# can_hub2.net
KiCad netlist of a schematic drawn in EAGLE
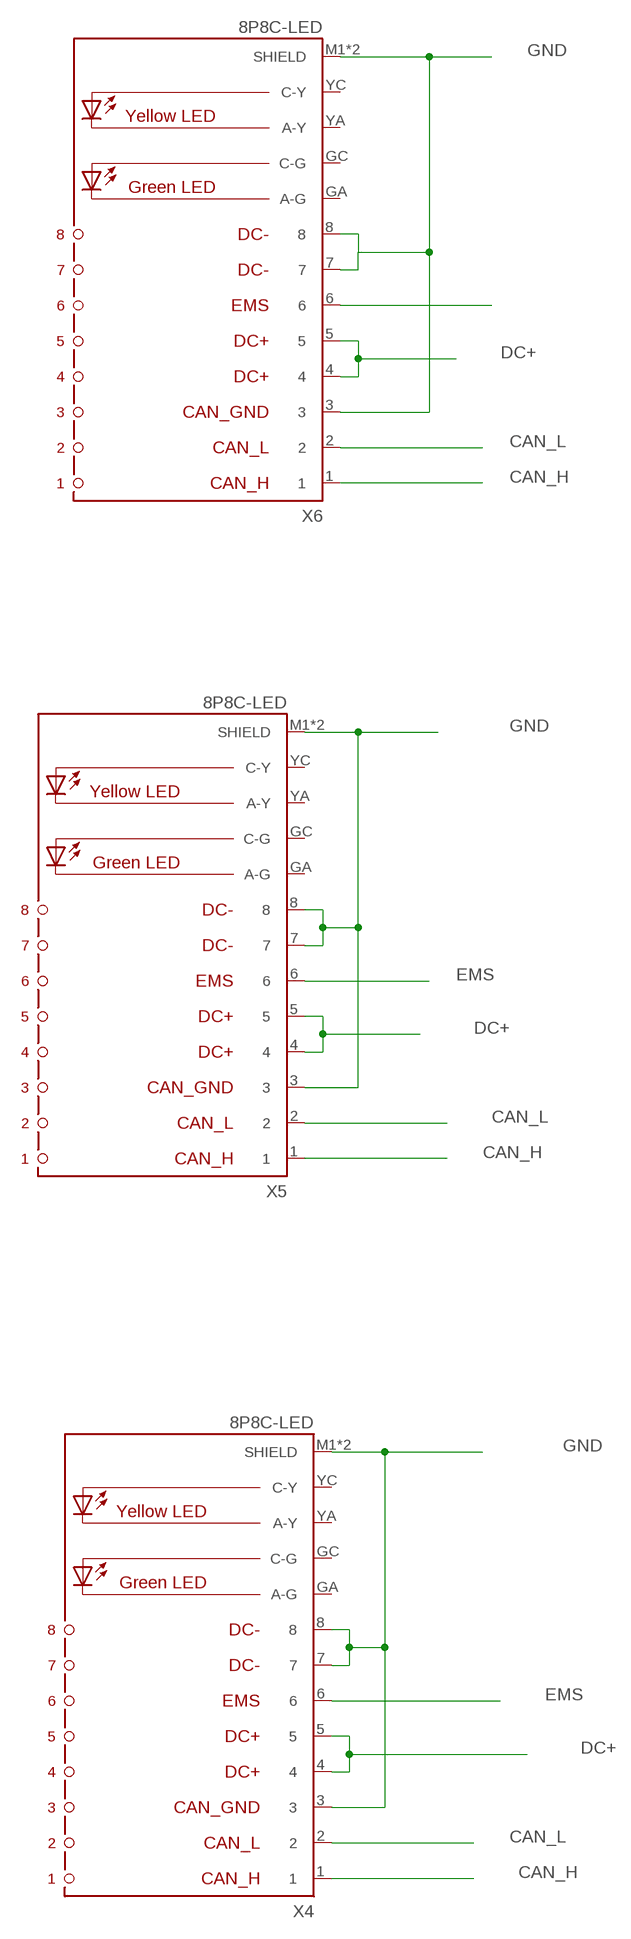
[diagram p0: schematic, sheet 1, part 1 of 3]
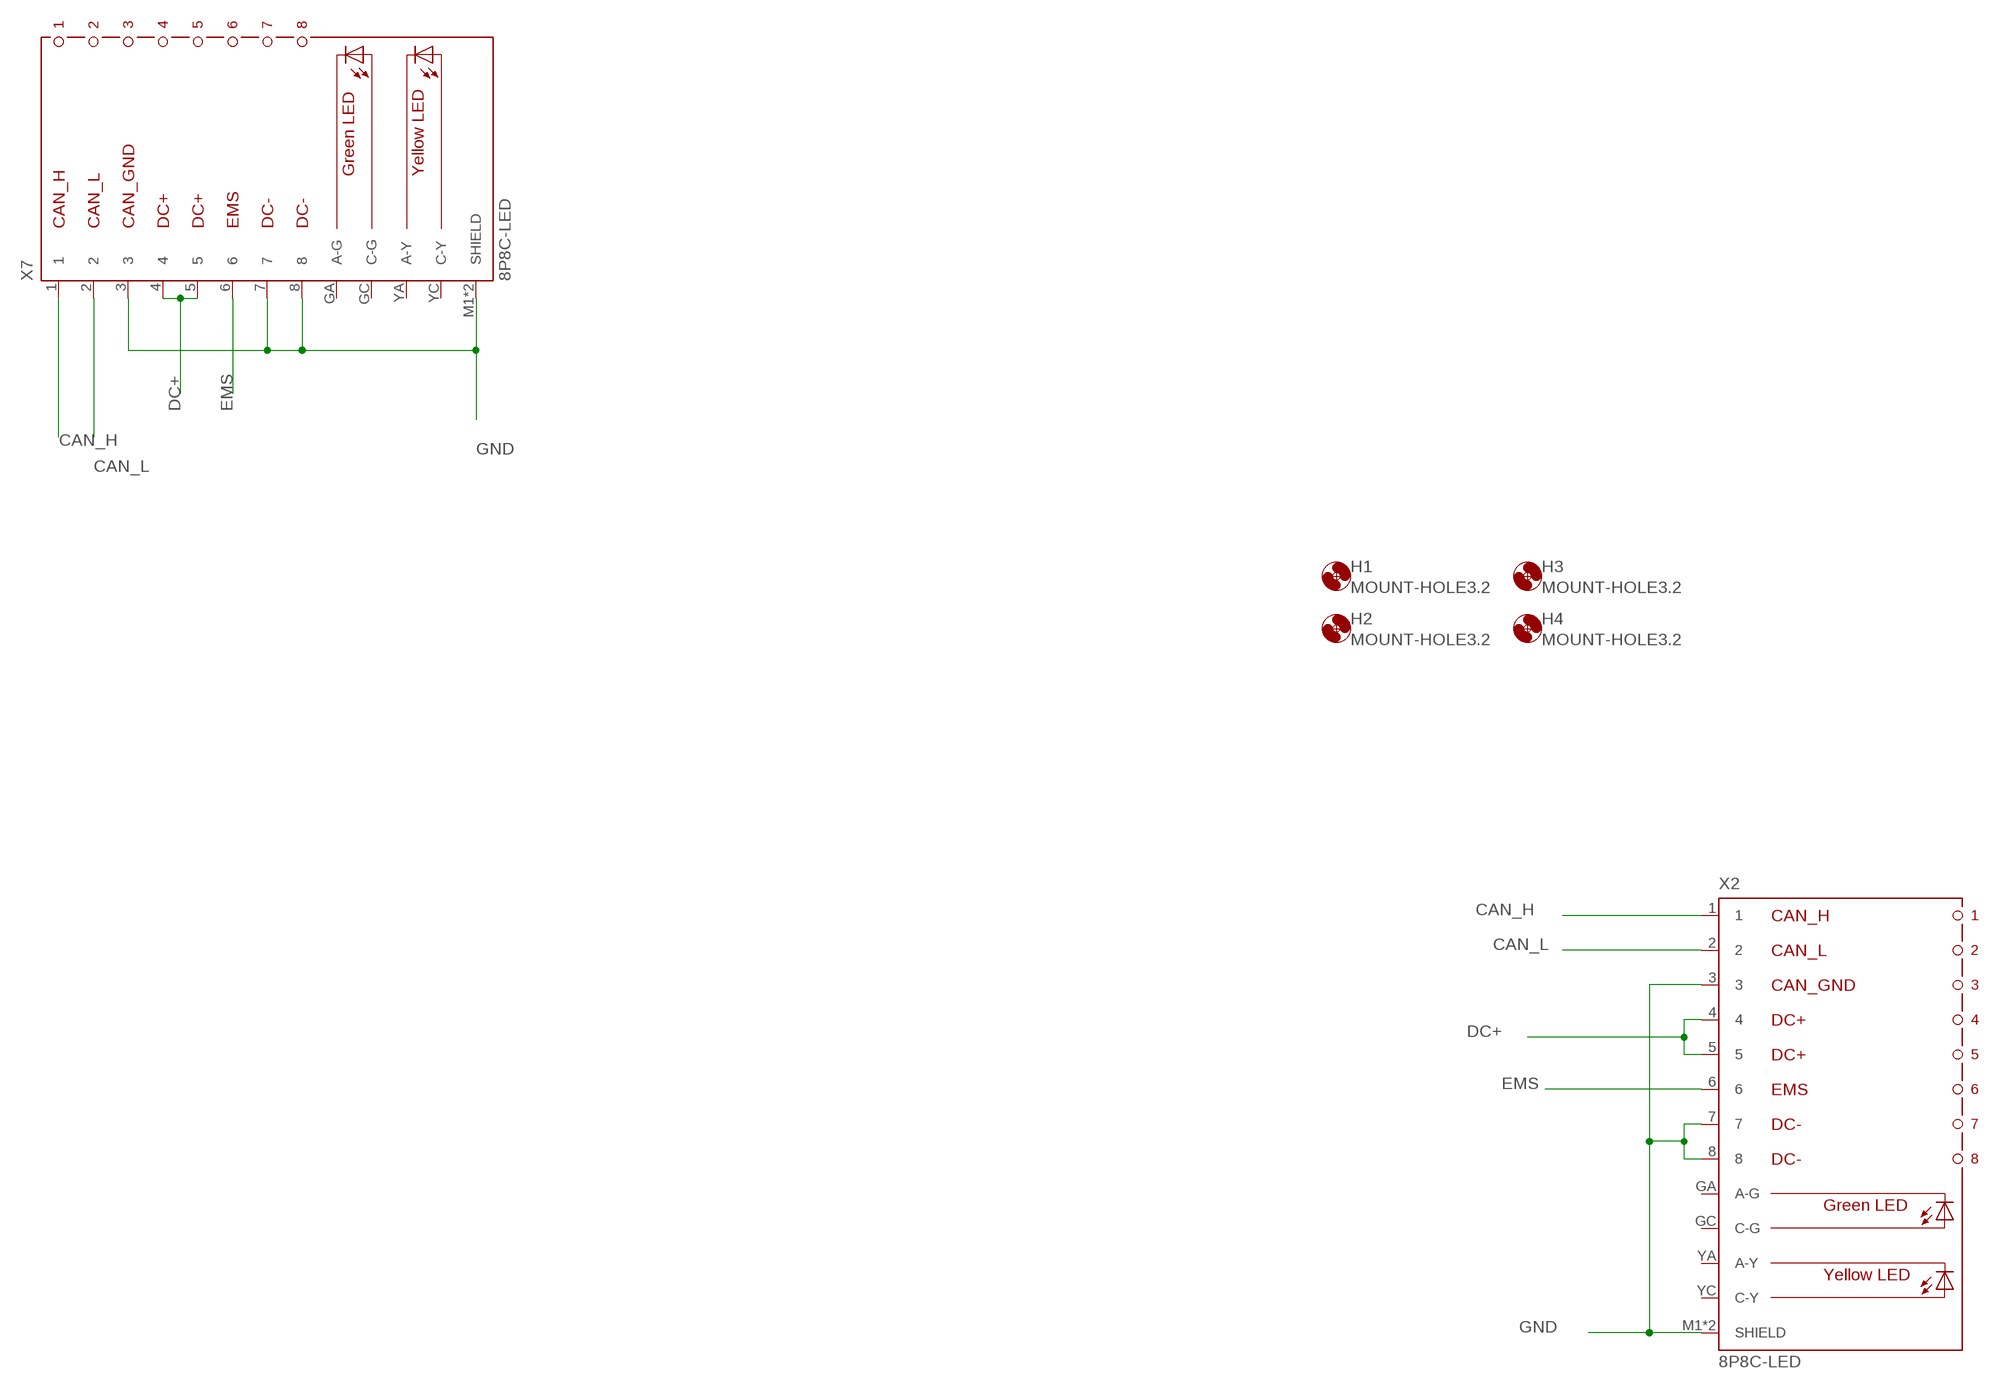
[diagram p1: schematic, sheet 1, part 2 of 3]
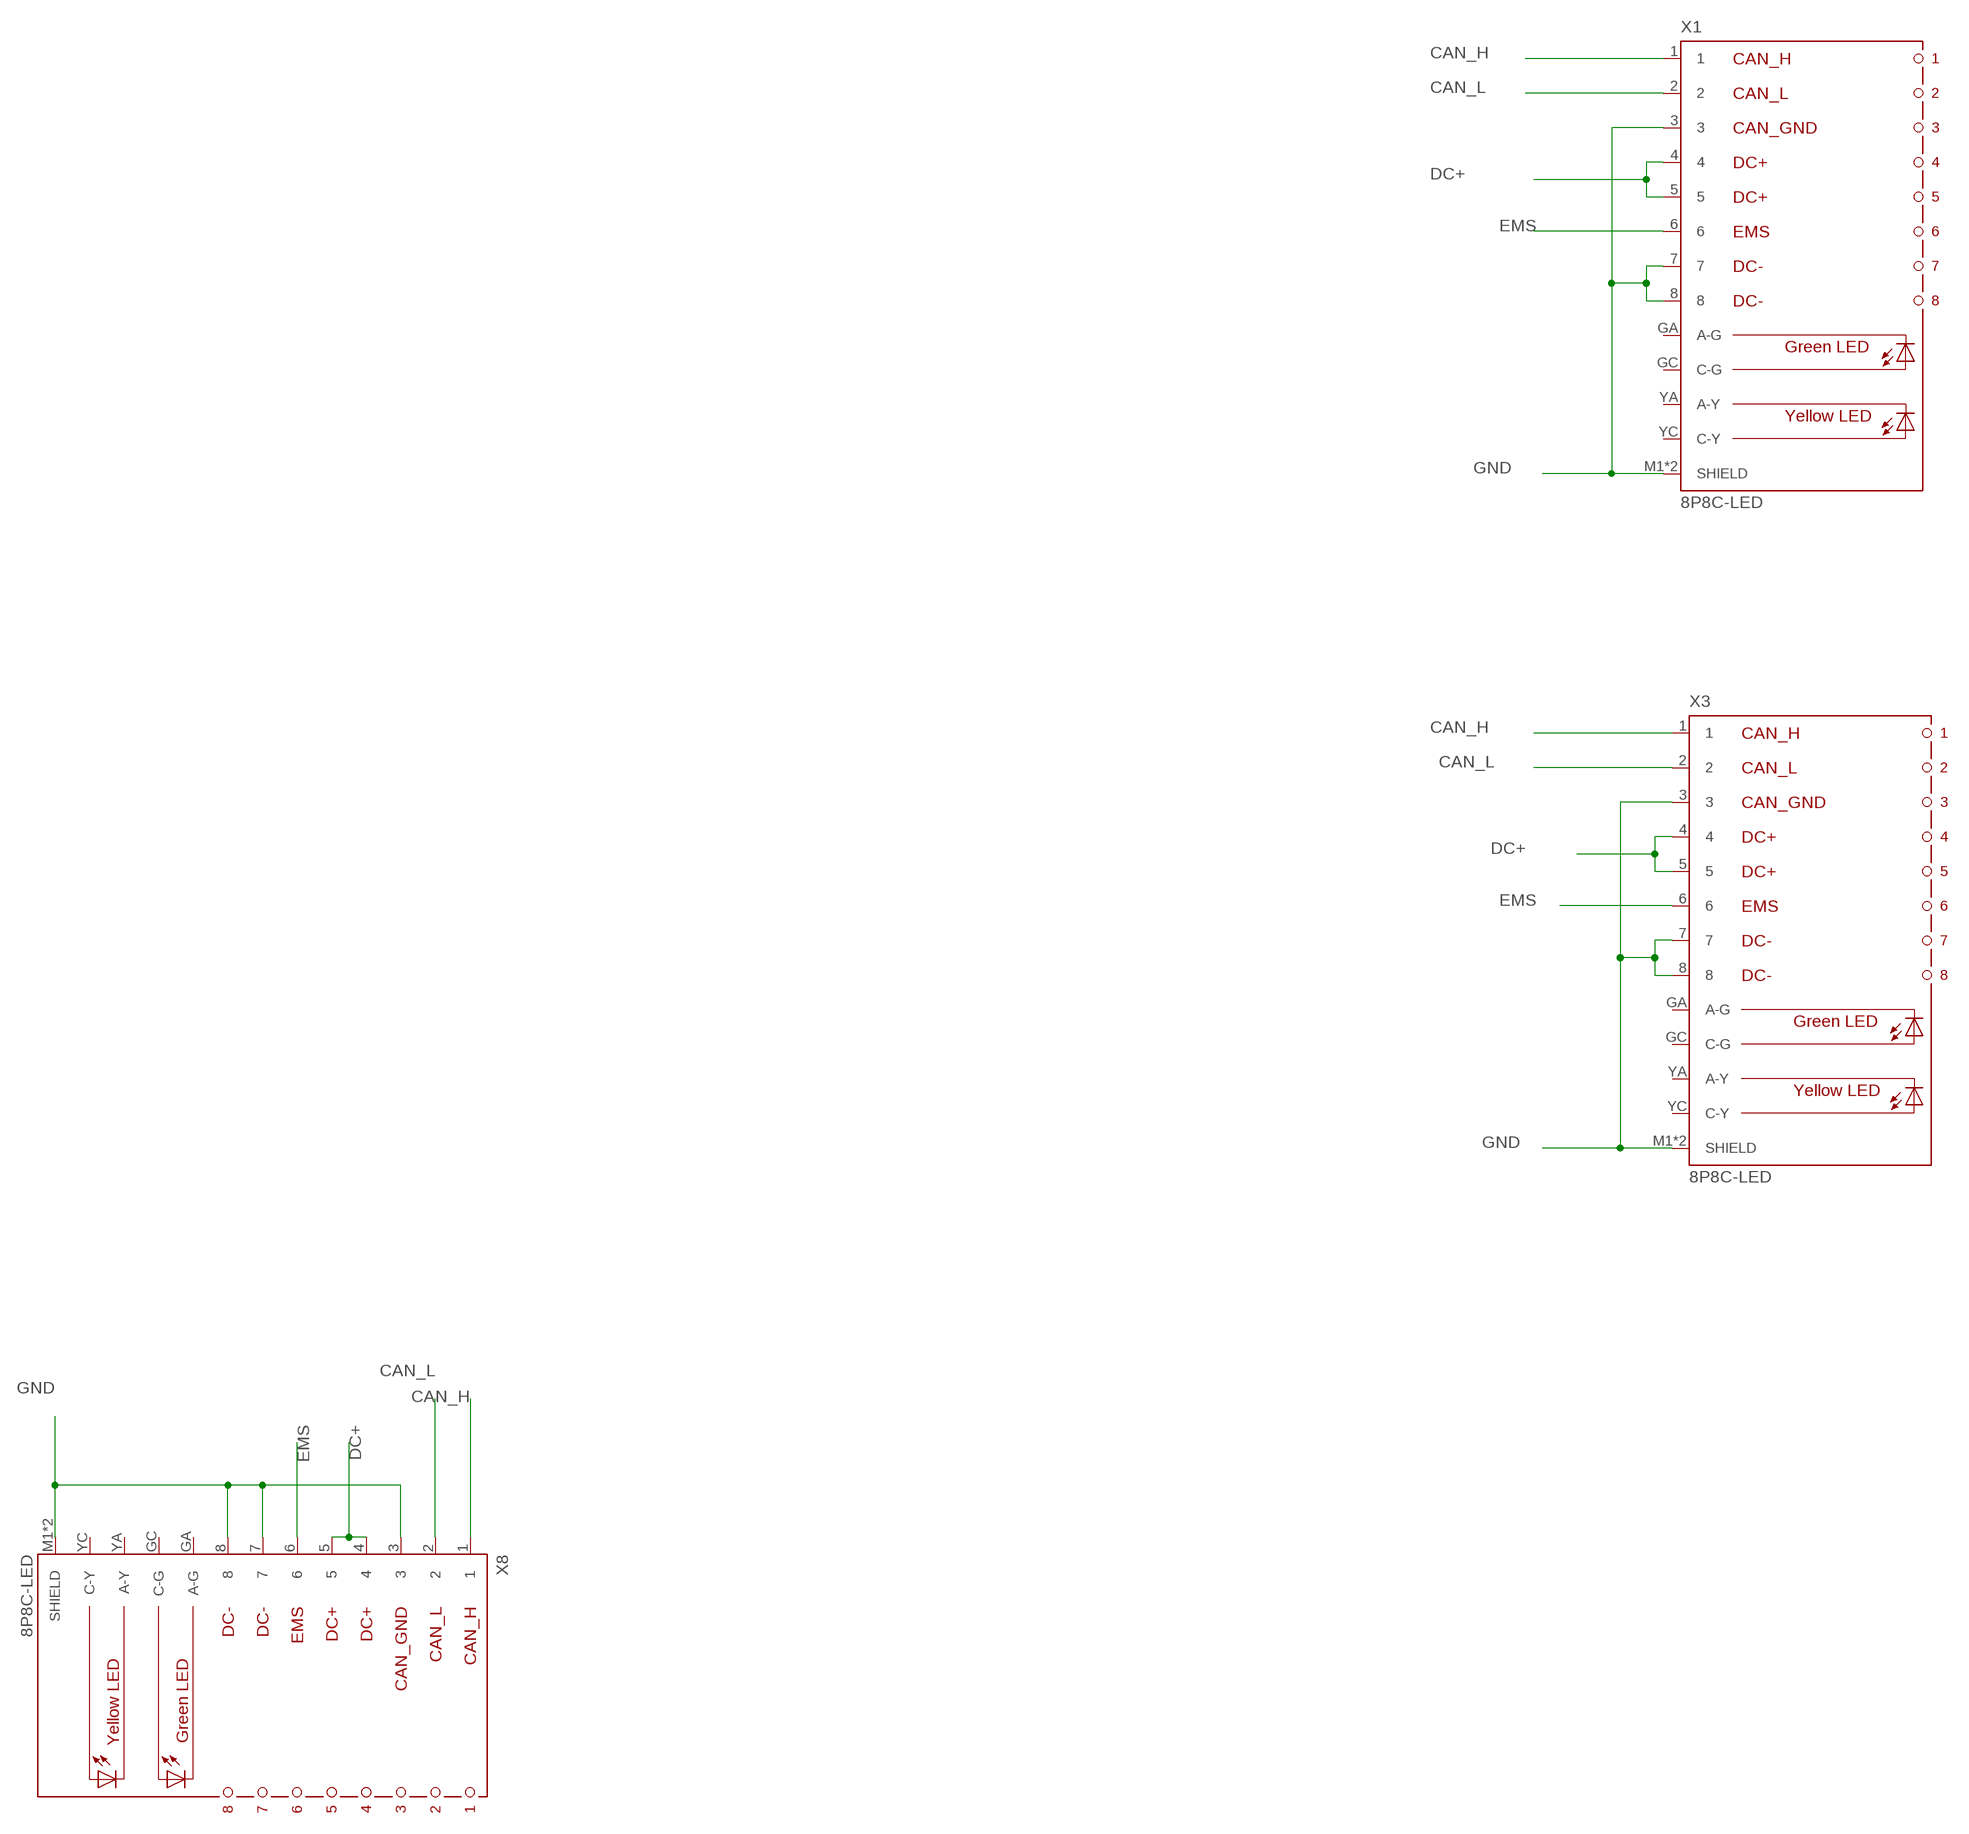
[diagram p2: schematic, sheet 1, part 3 of 3]

(export (version "E")
  (design (tool "Eeschema 10.0.6"))
  (components
    (comp (ref "H1")
      (value "MOUNT-HOLE3.2")
      (footprint "eagle-import:3,2")
      (libsource (lib "eagle-import") (part "MOUNT-HOLE3.2"))
    )
    (comp (ref "H2")
      (value "MOUNT-HOLE3.2")
      (footprint "eagle-import:3,2")
      (libsource (lib "eagle-import") (part "MOUNT-HOLE3.2"))
    )
    (comp (ref "H3")
      (value "MOUNT-HOLE3.2")
      (footprint "eagle-import:3,2")
      (libsource (lib "eagle-import") (part "MOUNT-HOLE3.2"))
    )
    (comp (ref "H4")
      (value "MOUNT-HOLE3.2")
      (footprint "eagle-import:3,2")
      (libsource (lib "eagle-import") (part "MOUNT-HOLE3.2"))
    )
    (comp (ref "X1")
      (value "8P8C-LED")
      (footprint "eagle-import:8P8C-LED")
      (libsource (lib "eagle-import") (part "8P8C-LED"))
    )
    (comp (ref "X2")
      (value "8P8C-LED")
      (footprint "eagle-import:8P8C-LED")
      (libsource (lib "eagle-import") (part "8P8C-LED"))
    )
    (comp (ref "X3")
      (value "8P8C-LED")
      (footprint "eagle-import:8P8C-LED")
      (libsource (lib "eagle-import") (part "8P8C-LED"))
    )
    (comp (ref "X4")
      (value "8P8C-LED")
      (footprint "eagle-import:8P8C-LED")
      (libsource (lib "eagle-import") (part "8P8C-LED"))
    )
    (comp (ref "X5")
      (value "8P8C-LED")
      (footprint "eagle-import:8P8C-LED")
      (libsource (lib "eagle-import") (part "8P8C-LED"))
    )
    (comp (ref "X6")
      (value "8P8C-LED")
      (footprint "eagle-import:8P8C-LED")
      (libsource (lib "eagle-import") (part "8P8C-LED"))
    )
    (comp (ref "X7")
      (value "8P8C-LED")
      (footprint "eagle-import:8P8C-LED")
      (libsource (lib "eagle-import") (part "8P8C-LED"))
    )
    (comp (ref "X8")
      (value "8P8C-LED")
      (footprint "eagle-import:8P8C-LED")
      (libsource (lib "eagle-import") (part "8P8C-LED"))
    )
  )
  (nets
    (net (code "1") (name "/CAN_H") (class "Default")
      (node (ref "X1") (pin "1") (pinfunction "1_1") (pintype "input"))
      (node (ref "X2") (pin "1") (pinfunction "1_1") (pintype "input"))
      (node (ref "X3") (pin "1") (pinfunction "1_1") (pintype "input"))
      (node (ref "X4") (pin "1") (pinfunction "1_1") (pintype "input"))
      (node (ref "X5") (pin "1") (pinfunction "1_1") (pintype "input"))
      (node (ref "X6") (pin "1") (pinfunction "1_1") (pintype "input"))
      (node (ref "X7") (pin "1") (pinfunction "1_1") (pintype "input"))
      (node (ref "X8") (pin "1") (pinfunction "1_1") (pintype "input"))
    )
    (net (code "2") (name "/CAN_L") (class "Default")
      (node (ref "X1") (pin "2") (pinfunction "2_2") (pintype "input"))
      (node (ref "X2") (pin "2") (pinfunction "2_2") (pintype "input"))
      (node (ref "X3") (pin "2") (pinfunction "2_2") (pintype "input"))
      (node (ref "X4") (pin "2") (pinfunction "2_2") (pintype "input"))
      (node (ref "X5") (pin "2") (pinfunction "2_2") (pintype "input"))
      (node (ref "X6") (pin "2") (pinfunction "2_2") (pintype "input"))
      (node (ref "X7") (pin "2") (pinfunction "2_2") (pintype "input"))
      (node (ref "X8") (pin "2") (pinfunction "2_2") (pintype "input"))
    )
    (net (code "3") (name "/DC+") (class "Default")
      (node (ref "X1") (pin "4") (pinfunction "4_4") (pintype "input"))
      (node (ref "X1") (pin "5") (pinfunction "5_5") (pintype "input"))
      (node (ref "X2") (pin "4") (pinfunction "4_4") (pintype "input"))
      (node (ref "X2") (pin "5") (pinfunction "5_5") (pintype "input"))
      (node (ref "X3") (pin "4") (pinfunction "4_4") (pintype "input"))
      (node (ref "X3") (pin "5") (pinfunction "5_5") (pintype "input"))
      (node (ref "X4") (pin "4") (pinfunction "4_4") (pintype "input"))
      (node (ref "X4") (pin "5") (pinfunction "5_5") (pintype "input"))
      (node (ref "X5") (pin "4") (pinfunction "4_4") (pintype "input"))
      (node (ref "X5") (pin "5") (pinfunction "5_5") (pintype "input"))
      (node (ref "X6") (pin "4") (pinfunction "4_4") (pintype "input"))
      (node (ref "X6") (pin "5") (pinfunction "5_5") (pintype "input"))
      (node (ref "X7") (pin "4") (pinfunction "4_4") (pintype "input"))
      (node (ref "X7") (pin "5") (pinfunction "5_5") (pintype "input"))
      (node (ref "X8") (pin "4") (pinfunction "4_4") (pintype "input"))
      (node (ref "X8") (pin "5") (pinfunction "5_5") (pintype "input"))
    )
    (net (code "4") (name "/EMS") (class "Default")
      (node (ref "X1") (pin "6") (pinfunction "6_6") (pintype "input"))
      (node (ref "X2") (pin "6") (pinfunction "6_6") (pintype "input"))
      (node (ref "X3") (pin "6") (pinfunction "6_6") (pintype "input"))
      (node (ref "X4") (pin "6") (pinfunction "6_6") (pintype "input"))
      (node (ref "X5") (pin "6") (pinfunction "6_6") (pintype "input"))
      (node (ref "X6") (pin "6") (pinfunction "6_6") (pintype "input"))
      (node (ref "X7") (pin "6") (pinfunction "6_6") (pintype "input"))
      (node (ref "X8") (pin "6") (pinfunction "6_6") (pintype "input"))
    )
    (net (code "5") (name "/GND") (class "Default")
      (node (ref "X1") (pin "3") (pinfunction "3_3") (pintype "input"))
      (node (ref "X1") (pin "7") (pinfunction "7_7") (pintype "input"))
      (node (ref "X1") (pin "8") (pinfunction "8_8") (pintype "input"))
      (node (ref "X1") (pin "M1") (pinfunction "SHIELD_M1") (pintype "passive"))
      (node (ref "X1") (pin "M2") (pinfunction "SHIELD_M2") (pintype "passive"))
      (node (ref "X2") (pin "3") (pinfunction "3_3") (pintype "input"))
      (node (ref "X2") (pin "7") (pinfunction "7_7") (pintype "input"))
      (node (ref "X2") (pin "8") (pinfunction "8_8") (pintype "input"))
      (node (ref "X2") (pin "M1") (pinfunction "SHIELD_M1") (pintype "passive"))
      (node (ref "X2") (pin "M2") (pinfunction "SHIELD_M2") (pintype "passive"))
      (node (ref "X3") (pin "3") (pinfunction "3_3") (pintype "input"))
      (node (ref "X3") (pin "7") (pinfunction "7_7") (pintype "input"))
      (node (ref "X3") (pin "8") (pinfunction "8_8") (pintype "input"))
      (node (ref "X3") (pin "M1") (pinfunction "SHIELD_M1") (pintype "passive"))
      (node (ref "X3") (pin "M2") (pinfunction "SHIELD_M2") (pintype "passive"))
      (node (ref "X4") (pin "3") (pinfunction "3_3") (pintype "input"))
      (node (ref "X4") (pin "7") (pinfunction "7_7") (pintype "input"))
      (node (ref "X4") (pin "8") (pinfunction "8_8") (pintype "input"))
      (node (ref "X4") (pin "M1") (pinfunction "SHIELD_M1") (pintype "passive"))
      (node (ref "X4") (pin "M2") (pinfunction "SHIELD_M2") (pintype "passive"))
      (node (ref "X5") (pin "3") (pinfunction "3_3") (pintype "input"))
      (node (ref "X5") (pin "7") (pinfunction "7_7") (pintype "input"))
      (node (ref "X5") (pin "8") (pinfunction "8_8") (pintype "input"))
      (node (ref "X5") (pin "M1") (pinfunction "SHIELD_M1") (pintype "passive"))
      (node (ref "X5") (pin "M2") (pinfunction "SHIELD_M2") (pintype "passive"))
      (node (ref "X6") (pin "3") (pinfunction "3_3") (pintype "input"))
      (node (ref "X6") (pin "7") (pinfunction "7_7") (pintype "input"))
      (node (ref "X6") (pin "8") (pinfunction "8_8") (pintype "input"))
      (node (ref "X6") (pin "M1") (pinfunction "SHIELD_M1") (pintype "passive"))
      (node (ref "X6") (pin "M2") (pinfunction "SHIELD_M2") (pintype "passive"))
      (node (ref "X7") (pin "3") (pinfunction "3_3") (pintype "input"))
      (node (ref "X7") (pin "7") (pinfunction "7_7") (pintype "input"))
      (node (ref "X7") (pin "8") (pinfunction "8_8") (pintype "input"))
      (node (ref "X7") (pin "M1") (pinfunction "SHIELD_M1") (pintype "passive"))
      (node (ref "X7") (pin "M2") (pinfunction "SHIELD_M2") (pintype "passive"))
      (node (ref "X8") (pin "3") (pinfunction "3_3") (pintype "input"))
      (node (ref "X8") (pin "7") (pinfunction "7_7") (pintype "input"))
      (node (ref "X8") (pin "8") (pinfunction "8_8") (pintype "input"))
      (node (ref "X8") (pin "M1") (pinfunction "SHIELD_M1") (pintype "passive"))
      (node (ref "X8") (pin "M2") (pinfunction "SHIELD_M2") (pintype "passive"))
    )
    (net (code "6") (name "unconnected-(X1-A-G-PadGA)") (class "Default")
      (node (ref "X1") (pin "GA") (pinfunction "A-G_GA") (pintype "passive"))
    )
    (net (code "7") (name "unconnected-(X1-A-Y-PadYA)") (class "Default")
      (node (ref "X1") (pin "YA") (pinfunction "A-Y_YA") (pintype "passive"))
    )
    (net (code "8") (name "unconnected-(X1-C-G-PadGC)") (class "Default")
      (node (ref "X1") (pin "GC") (pinfunction "C-G_GC") (pintype "passive"))
    )
    (net (code "9") (name "unconnected-(X1-C-Y-PadYC)") (class "Default")
      (node (ref "X1") (pin "YC") (pinfunction "C-Y_YC") (pintype "passive"))
    )
    (net (code "10") (name "unconnected-(X2-A-G-PadGA)") (class "Default")
      (node (ref "X2") (pin "GA") (pinfunction "A-G_GA") (pintype "passive"))
    )
    (net (code "11") (name "unconnected-(X2-A-Y-PadYA)") (class "Default")
      (node (ref "X2") (pin "YA") (pinfunction "A-Y_YA") (pintype "passive"))
    )
    (net (code "12") (name "unconnected-(X2-C-G-PadGC)") (class "Default")
      (node (ref "X2") (pin "GC") (pinfunction "C-G_GC") (pintype "passive"))
    )
    (net (code "13") (name "unconnected-(X2-C-Y-PadYC)") (class "Default")
      (node (ref "X2") (pin "YC") (pinfunction "C-Y_YC") (pintype "passive"))
    )
    (net (code "14") (name "unconnected-(X3-A-G-PadGA)") (class "Default")
      (node (ref "X3") (pin "GA") (pinfunction "A-G_GA") (pintype "passive"))
    )
    (net (code "15") (name "unconnected-(X3-A-Y-PadYA)") (class "Default")
      (node (ref "X3") (pin "YA") (pinfunction "A-Y_YA") (pintype "passive"))
    )
    (net (code "16") (name "unconnected-(X3-C-G-PadGC)") (class "Default")
      (node (ref "X3") (pin "GC") (pinfunction "C-G_GC") (pintype "passive"))
    )
    (net (code "17") (name "unconnected-(X3-C-Y-PadYC)") (class "Default")
      (node (ref "X3") (pin "YC") (pinfunction "C-Y_YC") (pintype "passive"))
    )
    (net (code "18") (name "unconnected-(X4-A-G-PadGA)") (class "Default")
      (node (ref "X4") (pin "GA") (pinfunction "A-G_GA") (pintype "passive"))
    )
    (net (code "19") (name "unconnected-(X4-A-Y-PadYA)") (class "Default")
      (node (ref "X4") (pin "YA") (pinfunction "A-Y_YA") (pintype "passive"))
    )
    (net (code "20") (name "unconnected-(X4-C-G-PadGC)") (class "Default")
      (node (ref "X4") (pin "GC") (pinfunction "C-G_GC") (pintype "passive"))
    )
    (net (code "21") (name "unconnected-(X4-C-Y-PadYC)") (class "Default")
      (node (ref "X4") (pin "YC") (pinfunction "C-Y_YC") (pintype "passive"))
    )
    (net (code "22") (name "unconnected-(X5-A-G-PadGA)") (class "Default")
      (node (ref "X5") (pin "GA") (pinfunction "A-G_GA") (pintype "passive"))
    )
    (net (code "23") (name "unconnected-(X5-A-Y-PadYA)") (class "Default")
      (node (ref "X5") (pin "YA") (pinfunction "A-Y_YA") (pintype "passive"))
    )
    (net (code "24") (name "unconnected-(X5-C-G-PadGC)") (class "Default")
      (node (ref "X5") (pin "GC") (pinfunction "C-G_GC") (pintype "passive"))
    )
    (net (code "25") (name "unconnected-(X5-C-Y-PadYC)") (class "Default")
      (node (ref "X5") (pin "YC") (pinfunction "C-Y_YC") (pintype "passive"))
    )
    (net (code "26") (name "unconnected-(X6-A-G-PadGA)") (class "Default")
      (node (ref "X6") (pin "GA") (pinfunction "A-G_GA") (pintype "passive"))
    )
    (net (code "27") (name "unconnected-(X6-A-Y-PadYA)") (class "Default")
      (node (ref "X6") (pin "YA") (pinfunction "A-Y_YA") (pintype "passive"))
    )
    (net (code "28") (name "unconnected-(X6-C-G-PadGC)") (class "Default")
      (node (ref "X6") (pin "GC") (pinfunction "C-G_GC") (pintype "passive"))
    )
    (net (code "29") (name "unconnected-(X6-C-Y-PadYC)") (class "Default")
      (node (ref "X6") (pin "YC") (pinfunction "C-Y_YC") (pintype "passive"))
    )
    (net (code "30") (name "unconnected-(X7-A-G-PadGA)") (class "Default")
      (node (ref "X7") (pin "GA") (pinfunction "A-G_GA") (pintype "passive"))
    )
    (net (code "31") (name "unconnected-(X7-A-Y-PadYA)") (class "Default")
      (node (ref "X7") (pin "YA") (pinfunction "A-Y_YA") (pintype "passive"))
    )
    (net (code "32") (name "unconnected-(X7-C-G-PadGC)") (class "Default")
      (node (ref "X7") (pin "GC") (pinfunction "C-G_GC") (pintype "passive"))
    )
    (net (code "33") (name "unconnected-(X7-C-Y-PadYC)") (class "Default")
      (node (ref "X7") (pin "YC") (pinfunction "C-Y_YC") (pintype "passive"))
    )
    (net (code "34") (name "unconnected-(X8-A-G-PadGA)") (class "Default")
      (node (ref "X8") (pin "GA") (pinfunction "A-G_GA") (pintype "passive"))
    )
    (net (code "35") (name "unconnected-(X8-A-Y-PadYA)") (class "Default")
      (node (ref "X8") (pin "YA") (pinfunction "A-Y_YA") (pintype "passive"))
    )
    (net (code "36") (name "unconnected-(X8-C-G-PadGC)") (class "Default")
      (node (ref "X8") (pin "GC") (pinfunction "C-G_GC") (pintype "passive"))
    )
    (net (code "37") (name "unconnected-(X8-C-Y-PadYC)") (class "Default")
      (node (ref "X8") (pin "YC") (pinfunction "C-Y_YC") (pintype "passive"))
    )
  )
)
